# contactor-feedback.net
KiCad netlist of a schematic drawn in Altium Designer
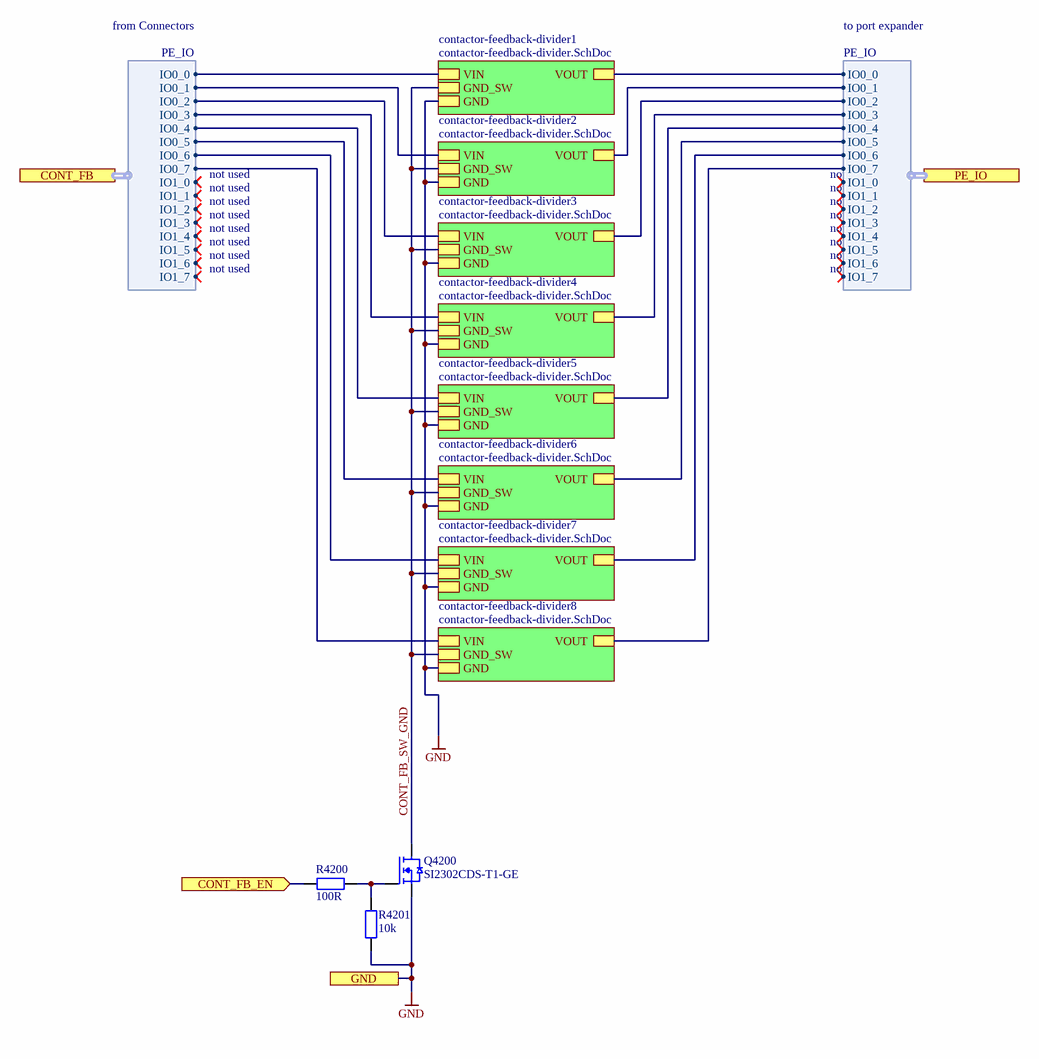
[diagram p0: contactor-feedback.SchDoc]

(export (version "E")
  (design (tool "Eeschema 10.0.6"))
  (components
    (comp (ref "Q4200")
      (value "SI2302CDS-T1-GE")
      (footprint "SOT95P237X112-3N")
      (description "MOSFET, N CHANNEL, 20V, 0.045OHM, 2.6A, TO-236")
      (fields (field (name "MANUFACTURER") "Vishay"))
      (libsource (lib "OE750") (part "NMOS"))
    )
    (comp (ref "R4200")
      (value "100R")
      (footprint "RESC1005X04N")
      (description "SMD Resistor 100R 0402")
      (fields (field (name "PART NUMBER") "gen_R_100R_0402") (field (name "TOLERANCE") "1%"))
      (libsource (lib "OE750") (part "R"))
    )
    (comp (ref "R4201")
      (value "10k")
      (footprint "RESC1005X04N")
      (description "SMD Resistor 10k 0402")
      (fields (field (name "PART NUMBER") "gen_R_10k_0402") (field (name "TOLERANCE") "1%"))
      (libsource (lib "OE750") (part "R"))
    )
  )
  (nets
    (net (code "2") (name "/CONT_FB_EN") (class "Default")
      (node (ref "R4200") (pin "1") (pinfunction "1_1") (pintype "passive"))
    )
    (net (code "3") (name "/CONT_FB_SW_GND") (class "Default")
      (node (ref "Q4200") (pin "D") (pinfunction "D_D") (pintype "passive"))
    )
    (net (code "21") (name "GND") (class "Default")
      (node (ref "Q4200") (pin "S") (pinfunction "S_S") (pintype "passive"))
      (node (ref "R4201") (pin "1") (pinfunction "1_1") (pintype "passive"))
    )
    (net (code "22") (name "Net-(Q4200-PadG)") (class "Default")
      (node (ref "Q4200") (pin "G") (pinfunction "G_G") (pintype "passive"))
      (node (ref "R4200") (pin "2") (pinfunction "2_2") (pintype "passive"))
      (node (ref "R4201") (pin "2") (pinfunction "2_2") (pintype "passive"))
    )
  )
)
